# MADcomboV2_2.net
KiCad netlist of a schematic drawn in EAGLE
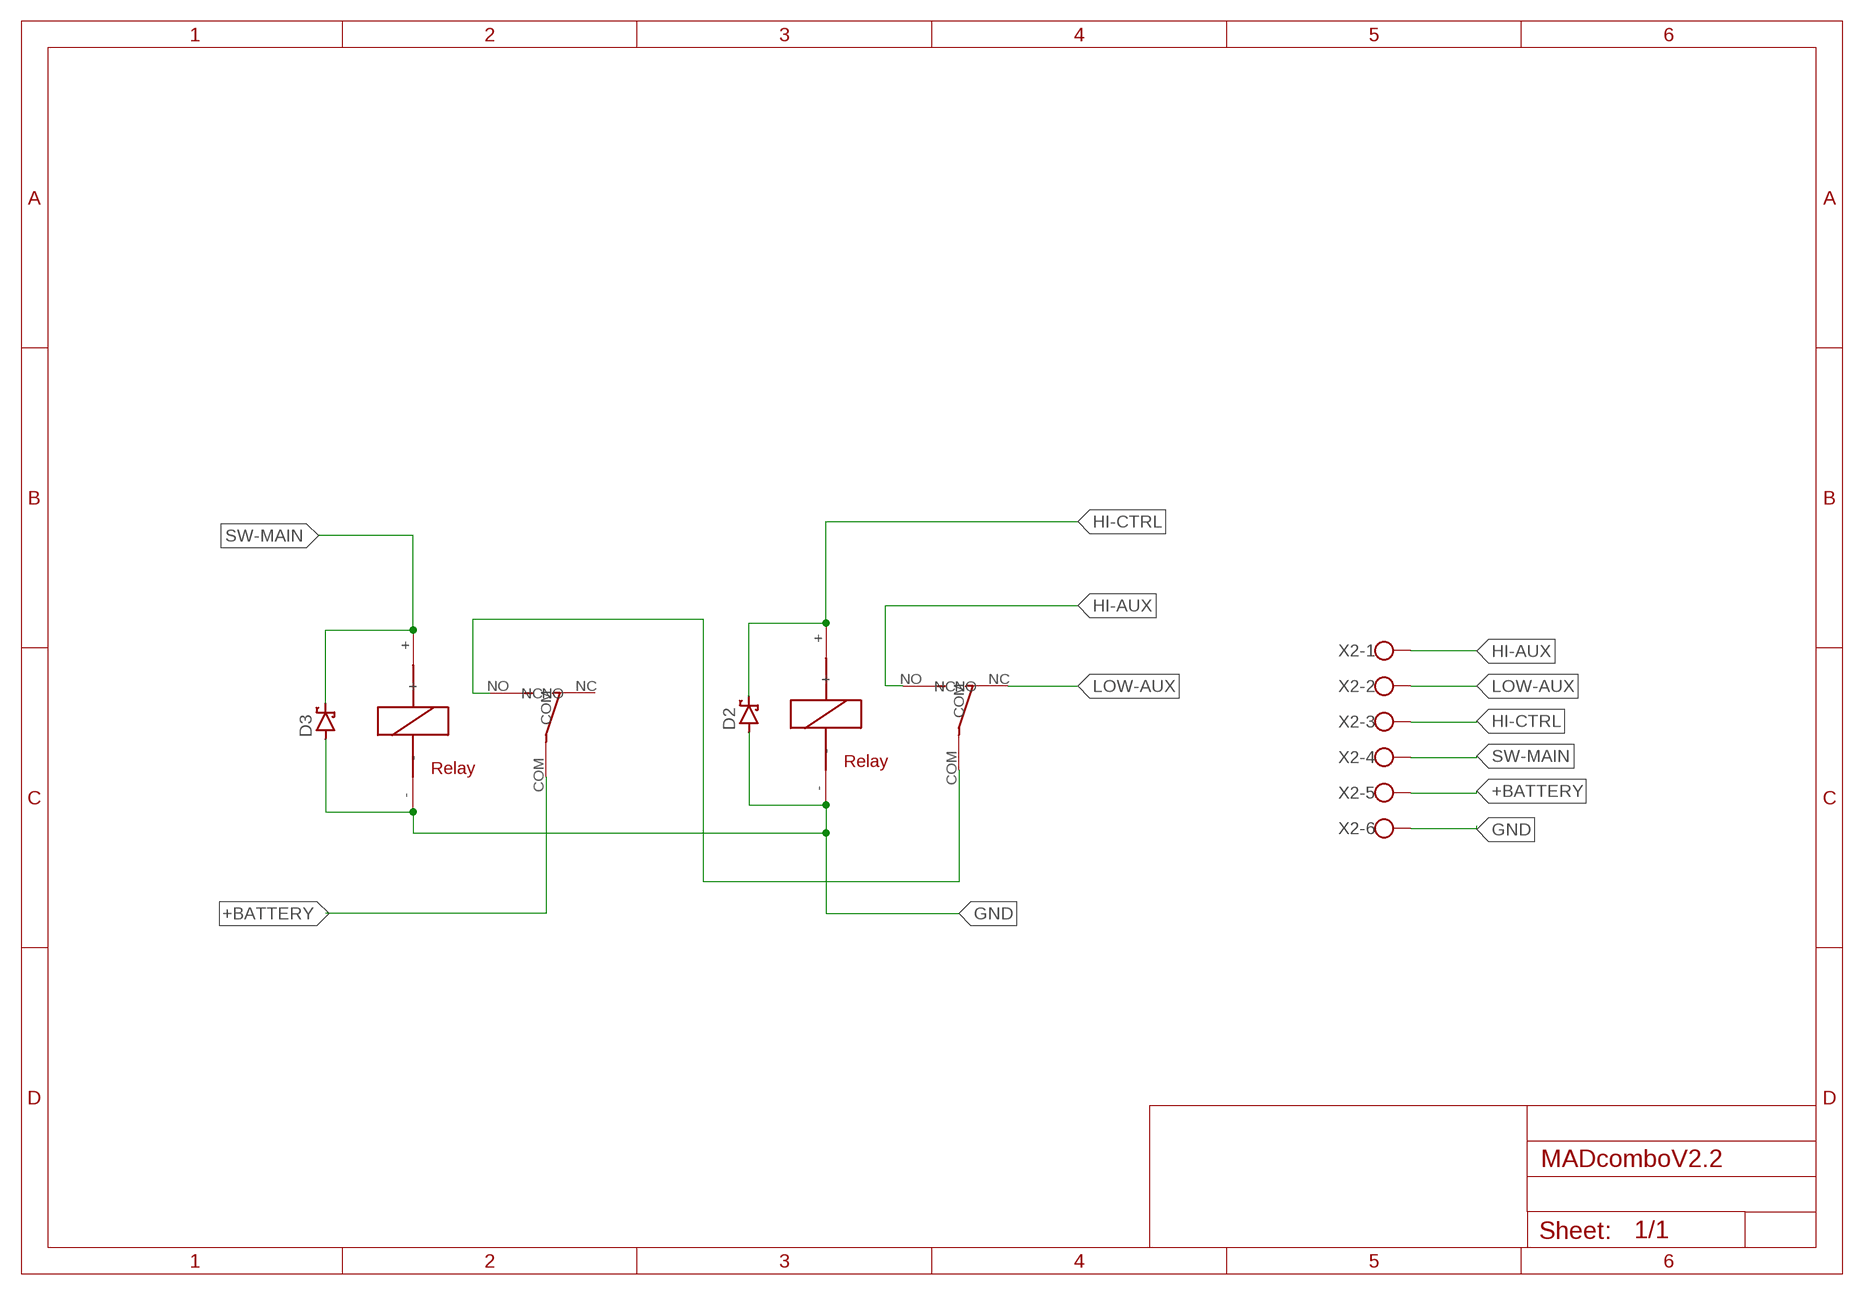
[diagram p0: schematic, sheet 1]

(export (version "E")
  (design (tool "Eeschema 10.0.6"))
  (components
    (comp (ref "D2")
      (value "SCHOTTKY-DIODESMD")
      (footprint "eagle-import:SMB")
      (libsource (lib "eagle-import") (part "SCHOTTKY-DIODESMD"))
    )
    (comp (ref "D3")
      (value "SCHOTTKY-DIODESMD")
      (footprint "eagle-import:SMB")
      (libsource (lib "eagle-import") (part "SCHOTTKY-DIODESMD"))
    )
    (comp (ref "U$3")
      (value "RELAY_MINI_SONGLE")
      (footprint "eagle-import:RELAY_MINI_SONGLE")
      (libsource (lib "eagle-import") (part "RELAY_MINI_SONGLE"))
    )
    (comp (ref "U$4")
      (value "RELAY_MINI_SONGLE")
      (footprint "eagle-import:RELAY_MINI_SONGLE")
      (libsource (lib "eagle-import") (part "RELAY_MINI_SONGLE"))
    )
    (comp (ref "X2")
      (value "W237-136")
      (footprint "eagle-import:W237-136")
      (fields (field (name "MPN") "237-136"))
      (libsource (lib "eagle-import") (part "W237-136"))
    )
  )
  (nets
    (net (code "1") (name "+BATTERY") (class "Default")
      (node (ref "U$3") (pin "COM") (pinfunction "COM_COM") (pintype "bidirectional"))
      (node (ref "X2") (pin "5") (pinfunction "KL_5") (pintype "passive"))
    )
    (net (code "2") (name "GND") (class "Default")
      (node (ref "D2") (pin "A") (pinfunction "A_A") (pintype "passive"))
      (node (ref "D3") (pin "A") (pinfunction "A_A") (pintype "passive"))
      (node (ref "U$3") (pin "-") (pinfunction "-_-") (pintype "bidirectional"))
      (node (ref "U$4") (pin "-") (pinfunction "-_-") (pintype "bidirectional"))
      (node (ref "X2") (pin "6") (pinfunction "KL_6") (pintype "passive"))
    )
    (net (code "3") (name "HI-AUX") (class "Default")
      (node (ref "U$4") (pin "NO") (pinfunction "NO_NO") (pintype "bidirectional"))
      (node (ref "X2") (pin "1") (pinfunction "KL_1") (pintype "passive"))
    )
    (net (code "4") (name "HI-CTRL") (class "Default")
      (node (ref "D2") (pin "C") (pinfunction "C_C") (pintype "passive"))
      (node (ref "U$4") (pin "+") (pinfunction "+_+") (pintype "bidirectional"))
      (node (ref "X2") (pin "3") (pinfunction "KL_3") (pintype "passive"))
    )
    (net (code "5") (name "LOW-AUX") (class "Default")
      (node (ref "U$4") (pin "NC") (pinfunction "NC_NC") (pintype "bidirectional"))
      (node (ref "X2") (pin "2") (pinfunction "KL_2") (pintype "passive"))
    )
    (net (code "6") (name "Net-(U$3-PadNO)") (class "Default")
      (node (ref "U$3") (pin "NO") (pinfunction "NO_NO") (pintype "bidirectional"))
      (node (ref "U$4") (pin "COM") (pinfunction "COM_COM") (pintype "bidirectional"))
    )
    (net (code "7") (name "SW-MAIN") (class "Default")
      (node (ref "D3") (pin "C") (pinfunction "C_C") (pintype "passive"))
      (node (ref "U$3") (pin "+") (pinfunction "+_+") (pintype "bidirectional"))
      (node (ref "X2") (pin "4") (pinfunction "KL_4") (pintype "passive"))
    )
    (net (code "8") (name "unconnected-(U$3-PadNC)") (class "Default")
      (node (ref "U$3") (pin "NC") (pinfunction "NC_NC") (pintype "bidirectional"))
    )
  )
)
